# 06-User_Interface.net
KiCad netlist of a schematic drawn in Altium Designer
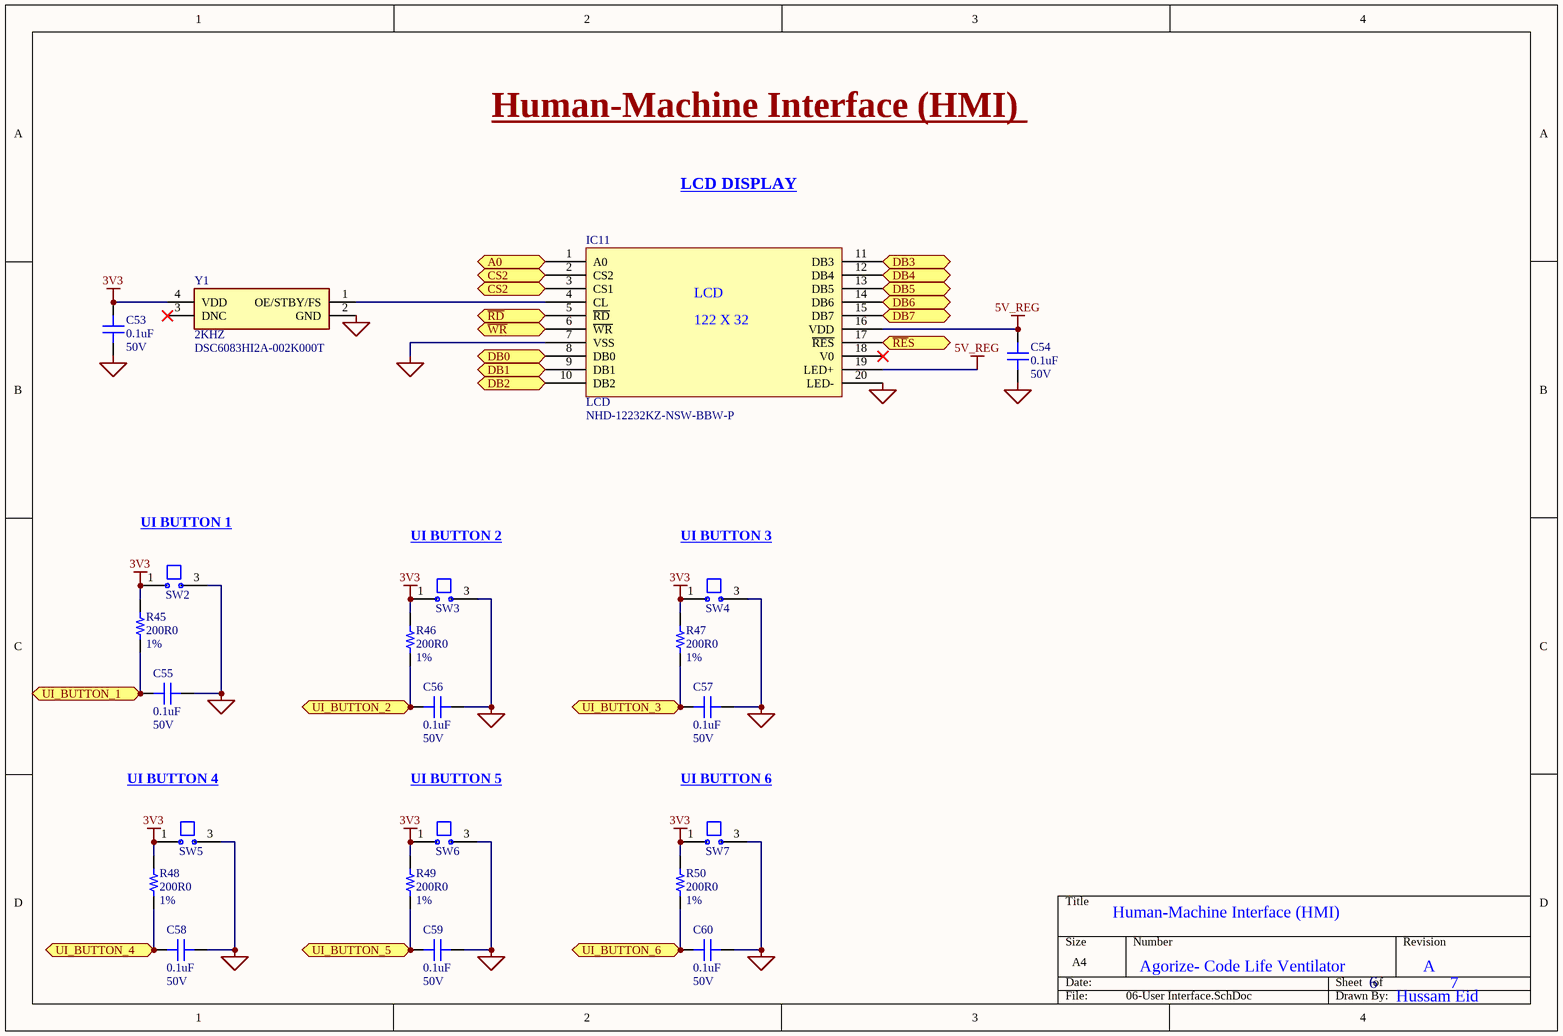
[diagram p0: 06-User Interface.SchDoc]

(export (version "E")
  (design (tool "Eeschema 10.0.6"))
  (components
    (comp (ref "C53")
      (value "0.1uF")
      (footprint "CAP 0603/1608")
      (description "CAP CER 0.1UF 50V X7R 0603")
      (fields (field (name "TOLERANCE") "20%") (field (name "VOLTAGE RATING") "50V"))
      (libsource (lib "Celestial Library Database") (part "Capacitor"))
    )
    (comp (ref "C54")
      (value "0.1uF")
      (footprint "CAP 0603/1608")
      (description "CAP CER 0.1UF 50V X7R 0603")
      (fields (field (name "TOLERANCE") "20%") (field (name "VOLTAGE RATING") "50V"))
      (libsource (lib "Celestial Library Database") (part "Capacitor"))
    )
    (comp (ref "C55")
      (value "0.1uF")
      (footprint "CAP 0603/1608")
      (description "CAP CER 0.1UF 50V X7R 0603")
      (fields (field (name "TOLERANCE") "20%") (field (name "VOLTAGE RATING") "50V"))
      (libsource (lib "Celestial Library Database") (part "Capacitor"))
    )
    (comp (ref "C56")
      (value "0.1uF")
      (footprint "CAP 0603/1608")
      (description "CAP CER 0.1UF 50V X7R 0603")
      (fields (field (name "TOLERANCE") "20%") (field (name "VOLTAGE RATING") "50V"))
      (libsource (lib "Celestial Library Database") (part "Capacitor"))
    )
    (comp (ref "C57")
      (value "0.1uF")
      (footprint "CAP 0603/1608")
      (description "CAP CER 0.1UF 50V X7R 0603")
      (fields (field (name "TOLERANCE") "20%") (field (name "VOLTAGE RATING") "50V"))
      (libsource (lib "Celestial Library Database") (part "Capacitor"))
    )
    (comp (ref "C58")
      (value "0.1uF")
      (footprint "CAP 0603/1608")
      (description "CAP CER 0.1UF 50V X7R 0603")
      (fields (field (name "TOLERANCE") "20%") (field (name "VOLTAGE RATING") "50V"))
      (libsource (lib "Celestial Library Database") (part "Capacitor"))
    )
    (comp (ref "C59")
      (value "0.1uF")
      (footprint "CAP 0603/1608")
      (description "CAP CER 0.1UF 50V X7R 0603")
      (fields (field (name "TOLERANCE") "20%") (field (name "VOLTAGE RATING") "50V"))
      (libsource (lib "Celestial Library Database") (part "Capacitor"))
    )
    (comp (ref "C60")
      (value "0.1uF")
      (footprint "CAP 0603/1608")
      (description "CAP CER 0.1UF 50V X7R 0603")
      (fields (field (name "TOLERANCE") "20%") (field (name "VOLTAGE RATING") "50V"))
      (libsource (lib "Celestial Library Database") (part "Capacitor"))
    )
    (comp (ref "IC11")
      (value "LCD")
      (footprint "DIP20")
      (description "LCD MOD GRAPH 122X32 WH TRANSM")
      (fields (field (name "MANUFACTURER PART NUMBER 1") "NHD-12232KZ-NSW-BBW-P"))
      (libsource (lib "Schlib1") (part "Component_1"))
    )
    (comp (ref "R45")
      (value "200R0")
      (footprint "RES 1206/3216")
      (description "RES SMD 10K OHM 1% 1/4W 1206")
      (fields (field (name "TOLERANCE") "1%"))
      (libsource (lib "Celestial Library Database") (part "Resistor"))
    )
    (comp (ref "R46")
      (value "200R0")
      (footprint "RES 1206/3216")
      (description "RES SMD 10K OHM 1% 1/4W 1206")
      (fields (field (name "TOLERANCE") "1%"))
      (libsource (lib "Celestial Library Database") (part "Resistor"))
    )
    (comp (ref "R47")
      (value "200R0")
      (footprint "RES 1206/3216")
      (description "RES SMD 10K OHM 1% 1/4W 1206")
      (fields (field (name "TOLERANCE") "1%"))
      (libsource (lib "Celestial Library Database") (part "Resistor"))
    )
    (comp (ref "R48")
      (value "200R0")
      (footprint "RES 1206/3216")
      (description "RES SMD 10K OHM 1% 1/4W 1206")
      (fields (field (name "TOLERANCE") "1%"))
      (libsource (lib "Celestial Library Database") (part "Resistor"))
    )
    (comp (ref "R49")
      (value "200R0")
      (footprint "RES 1206/3216")
      (description "RES SMD 10K OHM 1% 1/4W 1206")
      (fields (field (name "TOLERANCE") "1%"))
      (libsource (lib "Celestial Library Database") (part "Resistor"))
    )
    (comp (ref "R50")
      (value "200R0")
      (footprint "RES 1206/3216")
      (description "RES SMD 10K OHM 1% 1/4W 1206")
      (fields (field (name "TOLERANCE") "1%"))
      (libsource (lib "Celestial Library Database") (part "Resistor"))
    )
    (comp (ref "SW2")
      (value "Tactle switch_1")
      (footprint "32001E11BLK")
      (description "SWITCH TACT SPST-NO 0.025A 50V")
      (libsource (lib "Schlib1") (part "Tactle switch_1"))
    )
    (comp (ref "SW3")
      (value "Tactle switch_1")
      (footprint "32001E11BLK")
      (description "SWITCH TACT SPST-NO 0.025A 50V")
      (libsource (lib "Schlib1") (part "Tactle switch_1"))
    )
    (comp (ref "SW4")
      (value "Tactle switch_1")
      (footprint "32001E11BLK")
      (description "SWITCH TACT SPST-NO 0.025A 50V")
      (libsource (lib "Schlib1") (part "Tactle switch_1"))
    )
    (comp (ref "SW5")
      (value "Tactle switch_1")
      (footprint "32001E11BLK")
      (description "SWITCH TACT SPST-NO 0.025A 50V")
      (libsource (lib "Schlib1") (part "Tactle switch_1"))
    )
    (comp (ref "SW6")
      (value "Tactle switch_1")
      (footprint "32001E11BLK")
      (description "SWITCH TACT SPST-NO 0.025A 50V")
      (libsource (lib "Schlib1") (part "Tactle switch_1"))
    )
    (comp (ref "SW7")
      (value "Tactle switch_1")
      (footprint "32001E11BLK")
      (description "SWITCH TACT SPST-NO 0.025A 50V")
      (libsource (lib "Schlib1") (part "Tactle switch_1"))
    )
    (comp (ref "Y1")
      (value "2KHZ")
      (footprint "SamacSys:DSC6083HE1A032K800T")
      (description "MEMS OSC XO 2.0000KHZ CMOS SMD")
      (fields (field (name "MANUFACTURER PART NUMBER 1") "DSC6083HI2A-002K000T"))
      (libsource (lib "*") (part "DSC6083HE1A-032K800T"))
    )
  )
  (nets
    (net (code "1") (name "/A0") (class "Default")
      (node (ref "IC11") (pin "1") (pinfunction "A0_1") (pintype "passive"))
    )
    (net (code "2") (name "/CS2") (class "Default")
      (node (ref "IC11") (pin "2") (pinfunction "CS2_2") (pintype "passive"))
      (node (ref "IC11") (pin "3") (pinfunction "CS1_3") (pintype "passive"))
    )
    (net (code "3") (name "/DB0") (class "Default")
      (node (ref "IC11") (pin "8") (pinfunction "DB0_8") (pintype "passive"))
    )
    (net (code "4") (name "/DB1") (class "Default")
      (node (ref "IC11") (pin "9") (pinfunction "DB1_9") (pintype "passive"))
    )
    (net (code "5") (name "/DB2") (class "Default")
      (node (ref "IC11") (pin "10") (pinfunction "DB2_10") (pintype "passive"))
    )
    (net (code "6") (name "/DB3") (class "Default")
      (node (ref "IC11") (pin "11") (pinfunction "DB3_11") (pintype "passive"))
    )
    (net (code "7") (name "/DB4") (class "Default")
      (node (ref "IC11") (pin "12") (pinfunction "DB4_12") (pintype "passive"))
    )
    (net (code "8") (name "/DB5") (class "Default")
      (node (ref "IC11") (pin "13") (pinfunction "DB5_13") (pintype "passive"))
    )
    (net (code "9") (name "/DB6") (class "Default")
      (node (ref "IC11") (pin "14") (pinfunction "DB6_14") (pintype "passive"))
    )
    (net (code "10") (name "/DB7") (class "Default")
      (node (ref "IC11") (pin "15") (pinfunction "DB7_15") (pintype "passive"))
    )
    (net (code "11") (name "/UI_BUTTON_1") (class "Default")
      (node (ref "C55") (pin "1") (pinfunction "1_1") (pintype "passive"))
      (node (ref "R45") (pin "1") (pinfunction "1_1") (pintype "passive"))
    )
    (net (code "12") (name "/UI_BUTTON_2") (class "Default")
      (node (ref "C56") (pin "1") (pinfunction "1_1") (pintype "passive"))
      (node (ref "R46") (pin "1") (pinfunction "1_1") (pintype "passive"))
    )
    (net (code "13") (name "/UI_BUTTON_3") (class "Default")
      (node (ref "C57") (pin "1") (pinfunction "1_1") (pintype "passive"))
      (node (ref "R47") (pin "1") (pinfunction "1_1") (pintype "passive"))
    )
    (net (code "14") (name "/UI_BUTTON_4") (class "Default")
      (node (ref "C58") (pin "1") (pinfunction "1_1") (pintype "passive"))
      (node (ref "R48") (pin "1") (pinfunction "1_1") (pintype "passive"))
    )
    (net (code "15") (name "/UI_BUTTON_5") (class "Default")
      (node (ref "C59") (pin "1") (pinfunction "1_1") (pintype "passive"))
      (node (ref "R49") (pin "1") (pinfunction "1_1") (pintype "passive"))
    )
    (net (code "16") (name "/UI_BUTTON_6") (class "Default")
      (node (ref "C60") (pin "1") (pinfunction "1_1") (pintype "passive"))
      (node (ref "R50") (pin "1") (pinfunction "1_1") (pintype "passive"))
    )
    (net (code "17") (name "/~{RD}") (class "Default")
      (node (ref "IC11") (pin "5") (pinfunction "~{RD}_5") (pintype "passive"))
    )
    (net (code "18") (name "/~{RE}S") (class "Default")
      (node (ref "IC11") (pin "17") (pinfunction "~{RES}_17") (pintype "passive"))
    )
    (net (code "19") (name "/~{WR}") (class "Default")
      (node (ref "IC11") (pin "6") (pinfunction "~{WR}_6") (pintype "passive"))
    )
    (net (code "20") (name "3V3") (class "Default")
      (node (ref "C53") (pin "1") (pinfunction "1_1") (pintype "passive"))
      (node (ref "R45") (pin "2") (pinfunction "2_2") (pintype "passive"))
      (node (ref "R46") (pin "2") (pinfunction "2_2") (pintype "passive"))
      (node (ref "R47") (pin "2") (pinfunction "2_2") (pintype "passive"))
      (node (ref "R48") (pin "2") (pinfunction "2_2") (pintype "passive"))
      (node (ref "R49") (pin "2") (pinfunction "2_2") (pintype "passive"))
      (node (ref "R50") (pin "2") (pinfunction "2_2") (pintype "passive"))
      (node (ref "SW2") (pin "1") (pinfunction "1_1") (pintype "passive"))
      (node (ref "SW3") (pin "1") (pinfunction "1_1") (pintype "passive"))
      (node (ref "SW4") (pin "1") (pinfunction "1_1") (pintype "passive"))
      (node (ref "SW5") (pin "1") (pinfunction "1_1") (pintype "passive"))
      (node (ref "SW6") (pin "1") (pinfunction "1_1") (pintype "passive"))
      (node (ref "SW7") (pin "1") (pinfunction "1_1") (pintype "passive"))
      (node (ref "Y1") (pin "4") (pinfunction "VDD_4") (pintype "passive"))
    )
    (net (code "21") (name "5V_REG") (class "Default")
      (node (ref "C54") (pin "1") (pinfunction "1_1") (pintype "passive"))
      (node (ref "IC11") (pin "16") (pinfunction "VDD_16") (pintype "passive"))
      (node (ref "IC11") (pin "19") (pinfunction "LED+_19") (pintype "passive"))
    )
    (net (code "22") (name "COM") (class "Default")
      (node (ref "C53") (pin "2") (pinfunction "2_2") (pintype "passive"))
      (node (ref "C54") (pin "2") (pinfunction "2_2") (pintype "passive"))
      (node (ref "C55") (pin "2") (pinfunction "2_2") (pintype "passive"))
      (node (ref "C56") (pin "2") (pinfunction "2_2") (pintype "passive"))
      (node (ref "C57") (pin "2") (pinfunction "2_2") (pintype "passive"))
      (node (ref "C58") (pin "2") (pinfunction "2_2") (pintype "passive"))
      (node (ref "C59") (pin "2") (pinfunction "2_2") (pintype "passive"))
      (node (ref "C60") (pin "2") (pinfunction "2_2") (pintype "passive"))
      (node (ref "IC11") (pin "20") (pinfunction "LED-_20") (pintype "passive"))
      (node (ref "IC11") (pin "7") (pinfunction "VSS_7") (pintype "passive"))
      (node (ref "SW2") (pin "3") (pinfunction "3_3") (pintype "passive"))
      (node (ref "SW3") (pin "3") (pinfunction "3_3") (pintype "passive"))
      (node (ref "SW4") (pin "3") (pinfunction "3_3") (pintype "passive"))
      (node (ref "SW5") (pin "3") (pinfunction "3_3") (pintype "passive"))
      (node (ref "SW6") (pin "3") (pinfunction "3_3") (pintype "passive"))
      (node (ref "SW7") (pin "3") (pinfunction "3_3") (pintype "passive"))
      (node (ref "Y1") (pin "2") (pinfunction "GND_2") (pintype "passive"))
    )
    (net (code "23") (name "Net-(IC11-CL)") (class "Default")
      (node (ref "IC11") (pin "4") (pinfunction "CL_4") (pintype "passive"))
      (node (ref "Y1") (pin "1") (pinfunction "OE/STBY/FS_1") (pintype "passive"))
    )
    (net (code "24") (name "unconnected-(IC11-V0-Pad18)") (class "Default")
      (node (ref "IC11") (pin "18") (pinfunction "V0_18") (pintype "passive+no_connect"))
    )
    (net (code "25") (name "unconnected-(Y1-DNC-Pad3)") (class "Default")
      (node (ref "Y1") (pin "3") (pinfunction "DNC_3") (pintype "passive+no_connect"))
    )
  )
)
